# stm32_bob_v2.net
KiCad netlist of a schematic drawn in EAGLE
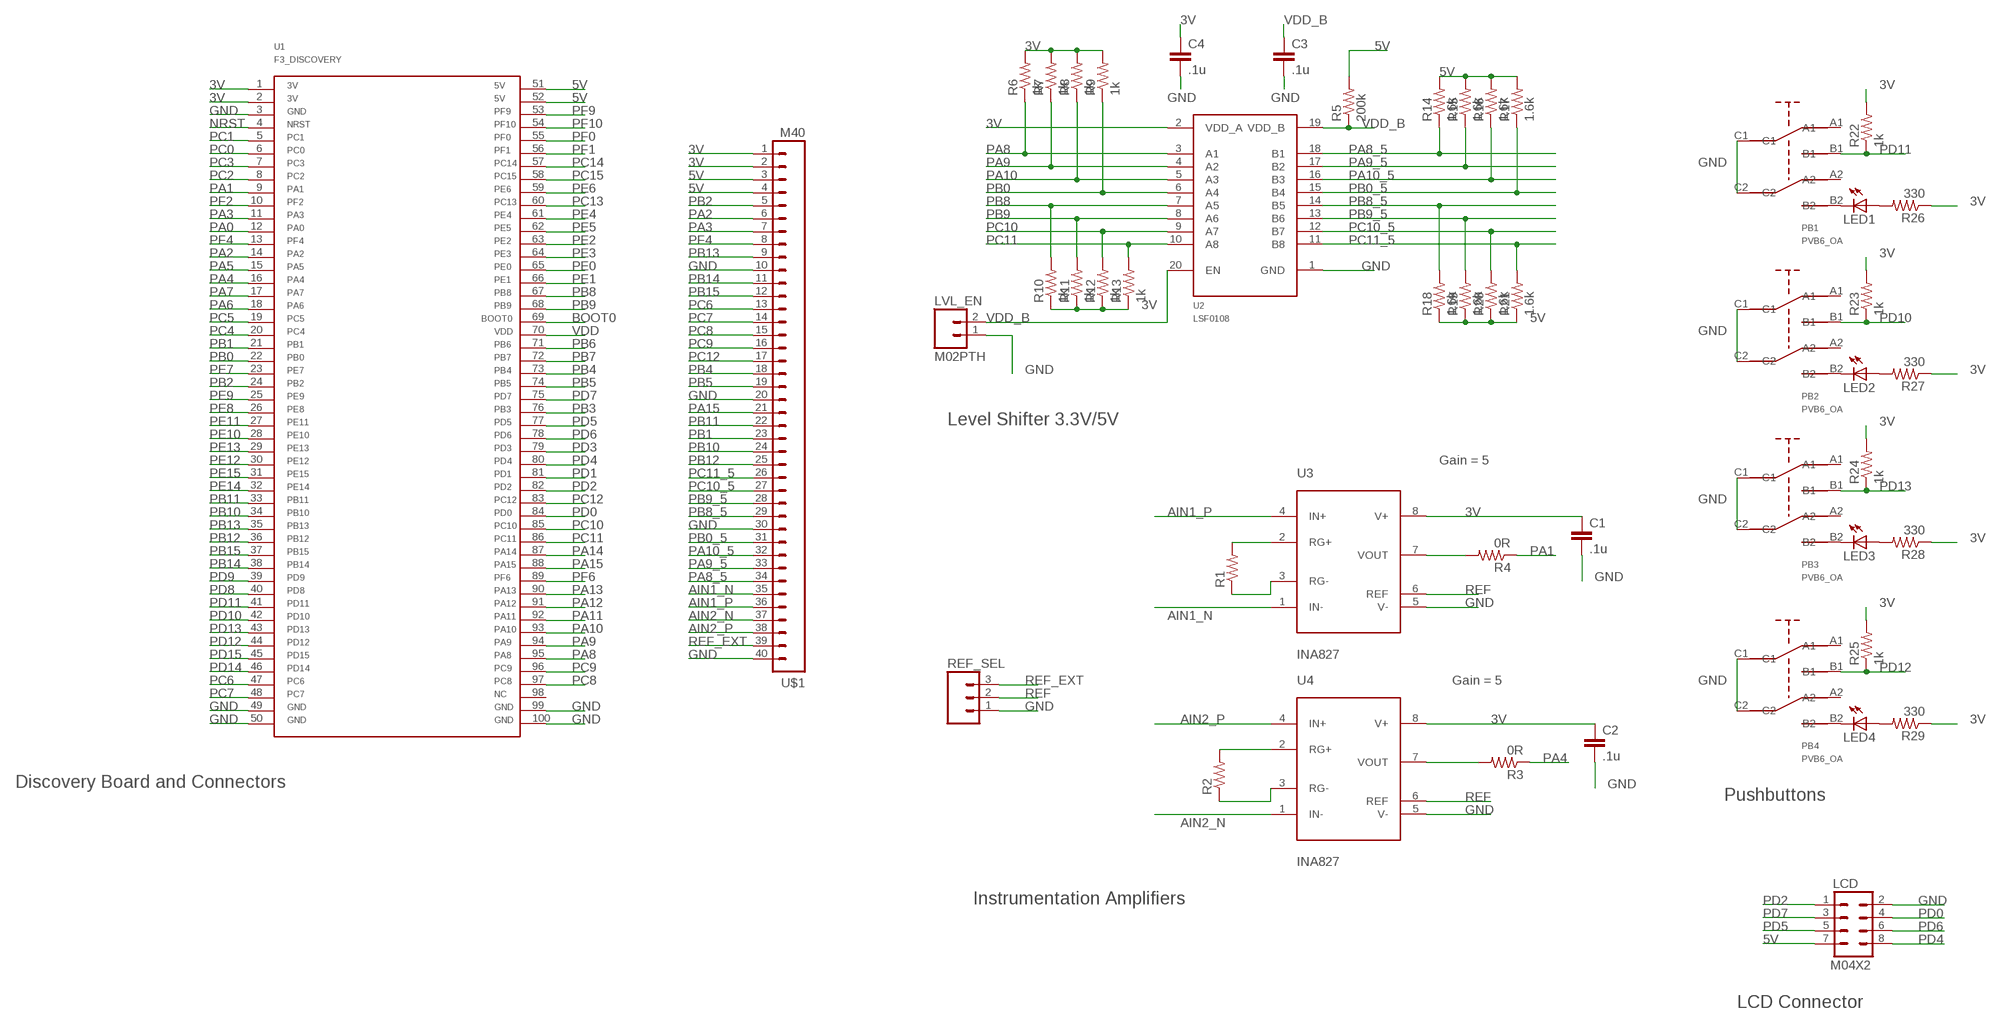
[diagram p0: schematic, sheet 1]

(export (version "E")
  (design (tool "Eeschema 10.0.6"))
  (components
    (comp (ref "C1")
      (value ".1u")
      (footprint "eagle-import:C0805")
      (libsource (lib "eagle-import") (part "C-EUC0805"))
    )
    (comp (ref "C2")
      (value ".1u")
      (footprint "eagle-import:C0805")
      (libsource (lib "eagle-import") (part "C-EUC0805"))
    )
    (comp (ref "C3")
      (value ".1u")
      (footprint "eagle-import:C0805")
      (libsource (lib "eagle-import") (part "C-EUC0805"))
    )
    (comp (ref "C4")
      (value ".1u")
      (footprint "eagle-import:C0805")
      (libsource (lib "eagle-import") (part "C-EUC0805"))
    )
    (comp (ref "LCD")
      (value "M04X2")
      (footprint "eagle-import:2X4")
      (libsource (lib "eagle-import") (part "M04X2"))
    )
    (comp (ref "LED1")
      (value "LED1206")
      (footprint "eagle-import:LED-1206")
      (libsource (lib "eagle-import") (part "LED1206"))
    )
    (comp (ref "LED2")
      (value "LED1206")
      (footprint "eagle-import:LED-1206")
      (libsource (lib "eagle-import") (part "LED1206"))
    )
    (comp (ref "LED3")
      (value "LED1206")
      (footprint "eagle-import:LED-1206")
      (libsource (lib "eagle-import") (part "LED1206"))
    )
    (comp (ref "LED4")
      (value "LED1206")
      (footprint "eagle-import:LED-1206")
      (libsource (lib "eagle-import") (part "LED1206"))
    )
    (comp (ref "LVL_EN")
      (value "M02PTH")
      (footprint "eagle-import:1X02")
      (libsource (lib "eagle-import") (part "M02PTH"))
    )
    (comp (ref "PB1")
      (value "PVB6_OA")
      (footprint "eagle-import:PVB6_OA")
      (libsource (lib "eagle-import") (part "PVB6_OA"))
    )
    (comp (ref "PB2")
      (value "PVB6_OA")
      (footprint "eagle-import:PVB6_OA")
      (libsource (lib "eagle-import") (part "PVB6_OA"))
    )
    (comp (ref "PB3")
      (value "PVB6_OA")
      (footprint "eagle-import:PVB6_OA")
      (libsource (lib "eagle-import") (part "PVB6_OA"))
    )
    (comp (ref "PB4")
      (value "PVB6_OA")
      (footprint "eagle-import:PVB6_OA")
      (libsource (lib "eagle-import") (part "PVB6_OA"))
    )
    (comp (ref "R1")
      (value "R-US_R1206")
      (footprint "eagle-import:R1206")
      (libsource (lib "eagle-import") (part "R-US_R1206"))
    )
    (comp (ref "R2")
      (value "R-US_R1206")
      (footprint "eagle-import:R1206")
      (libsource (lib "eagle-import") (part "R-US_R1206"))
    )
    (comp (ref "R3")
      (value "0R")
      (footprint "eagle-import:R1206")
      (libsource (lib "eagle-import") (part "R-US_R1206"))
    )
    (comp (ref "R4")
      (value "0R")
      (footprint "eagle-import:R1206")
      (libsource (lib "eagle-import") (part "R-US_R1206"))
    )
    (comp (ref "R5")
      (value "200k")
      (footprint "eagle-import:R0805")
      (libsource (lib "eagle-import") (part "R-US_R0805"))
    )
    (comp (ref "R6")
      (value "1k")
      (footprint "eagle-import:R0805")
      (libsource (lib "eagle-import") (part "R-US_R0805"))
    )
    (comp (ref "R7")
      (value "1k")
      (footprint "eagle-import:R0805")
      (libsource (lib "eagle-import") (part "R-US_R0805"))
    )
    (comp (ref "R8")
      (value "1k")
      (footprint "eagle-import:R0805")
      (libsource (lib "eagle-import") (part "R-US_R0805"))
    )
    (comp (ref "R9")
      (value "1k")
      (footprint "eagle-import:R0805")
      (libsource (lib "eagle-import") (part "R-US_R0805"))
    )
    (comp (ref "R10")
      (value "1k")
      (footprint "eagle-import:R0805")
      (libsource (lib "eagle-import") (part "R-US_R0805"))
    )
    (comp (ref "R11")
      (value "1k")
      (footprint "eagle-import:R0805")
      (libsource (lib "eagle-import") (part "R-US_R0805"))
    )
    (comp (ref "R12")
      (value "1k")
      (footprint "eagle-import:R0805")
      (libsource (lib "eagle-import") (part "R-US_R0805"))
    )
    (comp (ref "R13")
      (value "1k")
      (footprint "eagle-import:R0805")
      (libsource (lib "eagle-import") (part "R-US_R0805"))
    )
    (comp (ref "R14")
      (value "1.6k")
      (footprint "eagle-import:R0805")
      (libsource (lib "eagle-import") (part "R-US_R0805"))
    )
    (comp (ref "R15")
      (value "1.6k")
      (footprint "eagle-import:R0805")
      (libsource (lib "eagle-import") (part "R-US_R0805"))
    )
    (comp (ref "R16")
      (value "1.6k")
      (footprint "eagle-import:R0805")
      (libsource (lib "eagle-import") (part "R-US_R0805"))
    )
    (comp (ref "R17")
      (value "1.6k")
      (footprint "eagle-import:R0805")
      (libsource (lib "eagle-import") (part "R-US_R0805"))
    )
    (comp (ref "R18")
      (value "1.6k")
      (footprint "eagle-import:R0805")
      (libsource (lib "eagle-import") (part "R-US_R0805"))
    )
    (comp (ref "R19")
      (value "1.6k")
      (footprint "eagle-import:R0805")
      (libsource (lib "eagle-import") (part "R-US_R0805"))
    )
    (comp (ref "R20")
      (value "1.6k")
      (footprint "eagle-import:R0805")
      (libsource (lib "eagle-import") (part "R-US_R0805"))
    )
    (comp (ref "R21")
      (value "1.6k")
      (footprint "eagle-import:R0805")
      (libsource (lib "eagle-import") (part "R-US_R0805"))
    )
    (comp (ref "R22")
      (value "1k")
      (footprint "eagle-import:R0805")
      (libsource (lib "eagle-import") (part "R-US_R0805"))
    )
    (comp (ref "R23")
      (value "1k")
      (footprint "eagle-import:R0805")
      (libsource (lib "eagle-import") (part "R-US_R0805"))
    )
    (comp (ref "R24")
      (value "1k")
      (footprint "eagle-import:R0805")
      (libsource (lib "eagle-import") (part "R-US_R0805"))
    )
    (comp (ref "R25")
      (value "1k")
      (footprint "eagle-import:R0805")
      (libsource (lib "eagle-import") (part "R-US_R0805"))
    )
    (comp (ref "R26")
      (value "330")
      (footprint "eagle-import:R0805")
      (libsource (lib "eagle-import") (part "R-US_R0805"))
    )
    (comp (ref "R27")
      (value "330")
      (footprint "eagle-import:R0805")
      (libsource (lib "eagle-import") (part "R-US_R0805"))
    )
    (comp (ref "R28")
      (value "330")
      (footprint "eagle-import:R0805")
      (libsource (lib "eagle-import") (part "R-US_R0805"))
    )
    (comp (ref "R29")
      (value "330")
      (footprint "eagle-import:R0805")
      (libsource (lib "eagle-import") (part "R-US_R0805"))
    )
    (comp (ref "REF_SEL")
      (value "M03PTH")
      (footprint "eagle-import:1X03")
      (libsource (lib "eagle-import") (part "M03PTH"))
    )
    (comp (ref "U$1")
      (value "M40")
      (footprint "eagle-import:1X40")
      (libsource (lib "eagle-import") (part "M40"))
    )
    (comp (ref "U1")
      (value "F3_DISCOVERY")
      (footprint "eagle-import:F3_DISCOVERY")
      (libsource (lib "eagle-import") (part "F3_DISCOVERY"))
    )
    (comp (ref "U2")
      (value "LSF0108")
      (footprint "eagle-import:LSF0108")
      (libsource (lib "eagle-import") (part "LSF0108"))
    )
    (comp (ref "U3")
      (value "INA827")
      (footprint "eagle-import:MSOP8")
      (libsource (lib "eagle-import") (part "INA827"))
    )
    (comp (ref "U4")
      (value "INA827")
      (footprint "eagle-import:MSOP8")
      (libsource (lib "eagle-import") (part "INA827"))
    )
  )
  (nets
    (net (code "1") (name "/3V") (class "Default")
      (node (ref "C1") (pin "1") (pinfunction "1_1") (pintype "passive"))
      (node (ref "C2") (pin "1") (pinfunction "1_1") (pintype "passive"))
      (node (ref "C4") (pin "1") (pinfunction "1_1") (pintype "passive"))
      (node (ref "R10") (pin "1") (pinfunction "1_1") (pintype "passive"))
      (node (ref "R11") (pin "1") (pinfunction "1_1") (pintype "passive"))
      (node (ref "R12") (pin "1") (pinfunction "1_1") (pintype "passive"))
      (node (ref "R13") (pin "1") (pinfunction "1_1") (pintype "passive"))
      (node (ref "R22") (pin "2") (pinfunction "2_2") (pintype "passive"))
      (node (ref "R23") (pin "2") (pinfunction "2_2") (pintype "passive"))
      (node (ref "R24") (pin "2") (pinfunction "2_2") (pintype "passive"))
      (node (ref "R25") (pin "2") (pinfunction "2_2") (pintype "passive"))
      (node (ref "R26") (pin "1") (pinfunction "1_1") (pintype "passive"))
      (node (ref "R27") (pin "1") (pinfunction "1_1") (pintype "passive"))
      (node (ref "R28") (pin "1") (pinfunction "1_1") (pintype "passive"))
      (node (ref "R29") (pin "1") (pinfunction "1_1") (pintype "passive"))
      (node (ref "R6") (pin "2") (pinfunction "2_2") (pintype "passive"))
      (node (ref "R7") (pin "2") (pinfunction "2_2") (pintype "passive"))
      (node (ref "R8") (pin "2") (pinfunction "2_2") (pintype "passive"))
      (node (ref "R9") (pin "2") (pinfunction "2_2") (pintype "passive"))
      (node (ref "U$1") (pin "1") (pinfunction "1_1") (pintype "passive"))
      (node (ref "U$1") (pin "2") (pinfunction "2_2") (pintype "passive"))
      (node (ref "U1") (pin "1") (pinfunction "P$1_1") (pintype "bidirectional"))
      (node (ref "U1") (pin "2") (pinfunction "P$2_2") (pintype "bidirectional"))
      (node (ref "U2") (pin "2") (pinfunction "VDD_A_2") (pintype "bidirectional"))
      (node (ref "U3") (pin "8") (pinfunction "V+_8") (pintype "bidirectional"))
      (node (ref "U4") (pin "8") (pinfunction "V+_8") (pintype "bidirectional"))
    )
    (net (code "2") (name "/5V") (class "Default")
      (node (ref "LCD") (pin "7") (pinfunction "7_7") (pintype "passive"))
      (node (ref "R14") (pin "2") (pinfunction "2_2") (pintype "passive"))
      (node (ref "R15") (pin "2") (pinfunction "2_2") (pintype "passive"))
      (node (ref "R16") (pin "2") (pinfunction "2_2") (pintype "passive"))
      (node (ref "R17") (pin "2") (pinfunction "2_2") (pintype "passive"))
      (node (ref "R18") (pin "1") (pinfunction "1_1") (pintype "passive"))
      (node (ref "R19") (pin "1") (pinfunction "1_1") (pintype "passive"))
      (node (ref "R20") (pin "1") (pinfunction "1_1") (pintype "passive"))
      (node (ref "R21") (pin "1") (pinfunction "1_1") (pintype "passive"))
      (node (ref "R5") (pin "2") (pinfunction "2_2") (pintype "passive"))
      (node (ref "U$1") (pin "3") (pinfunction "3_3") (pintype "passive"))
      (node (ref "U$1") (pin "4") (pinfunction "4_4") (pintype "passive"))
      (node (ref "U1") (pin "51") (pinfunction "P$51_51") (pintype "bidirectional"))
      (node (ref "U1") (pin "52") (pinfunction "P$52_52") (pintype "bidirectional"))
    )
    (net (code "3") (name "/AIN1_N") (class "Default")
      (node (ref "U$1") (pin "35") (pinfunction "35_35") (pintype "passive"))
      (node (ref "U3") (pin "1") (pinfunction "IN-_1") (pintype "bidirectional"))
    )
    (net (code "4") (name "/AIN1_P") (class "Default")
      (node (ref "U$1") (pin "36") (pinfunction "36_36") (pintype "passive"))
      (node (ref "U3") (pin "4") (pinfunction "IN+_4") (pintype "bidirectional"))
    )
    (net (code "5") (name "/AIN2_N") (class "Default")
      (node (ref "U$1") (pin "37") (pinfunction "37_37") (pintype "passive"))
      (node (ref "U4") (pin "1") (pinfunction "IN-_1") (pintype "bidirectional"))
    )
    (net (code "6") (name "/AIN2_P") (class "Default")
      (node (ref "U$1") (pin "38") (pinfunction "38_38") (pintype "passive"))
      (node (ref "U4") (pin "4") (pinfunction "IN+_4") (pintype "bidirectional"))
    )
    (net (code "7") (name "/BOOT0") (class "Default")
      (node (ref "U1") (pin "69") (pinfunction "P$69_69") (pintype "bidirectional"))
    )
    (net (code "8") (name "/GND") (class "Default")
      (node (ref "C1") (pin "2") (pinfunction "2_2") (pintype "passive"))
      (node (ref "C2") (pin "2") (pinfunction "2_2") (pintype "passive"))
      (node (ref "C3") (pin "2") (pinfunction "2_2") (pintype "passive"))
      (node (ref "C4") (pin "2") (pinfunction "2_2") (pintype "passive"))
      (node (ref "LCD") (pin "2") (pinfunction "2_2") (pintype "passive"))
      (node (ref "LVL_EN") (pin "1") (pinfunction "1_1") (pintype "passive"))
      (node (ref "PB1") (pin "C1") (pinfunction "C1_C1") (pintype "bidirectional"))
      (node (ref "PB1") (pin "C2") (pinfunction "C2_C2") (pintype "bidirectional"))
      (node (ref "PB2") (pin "C1") (pinfunction "C1_C1") (pintype "bidirectional"))
      (node (ref "PB2") (pin "C2") (pinfunction "C2_C2") (pintype "bidirectional"))
      (node (ref "PB3") (pin "C1") (pinfunction "C1_C1") (pintype "bidirectional"))
      (node (ref "PB3") (pin "C2") (pinfunction "C2_C2") (pintype "bidirectional"))
      (node (ref "PB4") (pin "C1") (pinfunction "C1_C1") (pintype "bidirectional"))
      (node (ref "PB4") (pin "C2") (pinfunction "C2_C2") (pintype "bidirectional"))
      (node (ref "REF_SEL") (pin "1") (pinfunction "1_1") (pintype "passive"))
      (node (ref "U$1") (pin "10") (pinfunction "10_10") (pintype "passive"))
      (node (ref "U$1") (pin "20") (pinfunction "20_20") (pintype "passive"))
      (node (ref "U$1") (pin "30") (pinfunction "30_30") (pintype "passive"))
      (node (ref "U$1") (pin "40") (pinfunction "40_40") (pintype "passive"))
      (node (ref "U1") (pin "100") (pinfunction "P$100_100") (pintype "bidirectional"))
      (node (ref "U1") (pin "3") (pinfunction "P$3_3") (pintype "bidirectional"))
      (node (ref "U1") (pin "49") (pinfunction "P$49_49") (pintype "bidirectional"))
      (node (ref "U1") (pin "50") (pinfunction "P$50_50") (pintype "bidirectional"))
      (node (ref "U1") (pin "99") (pinfunction "P$99_99") (pintype "bidirectional"))
      (node (ref "U2") (pin "1") (pinfunction "GND_1") (pintype "bidirectional"))
      (node (ref "U3") (pin "5") (pinfunction "V-_5") (pintype "bidirectional"))
      (node (ref "U4") (pin "5") (pinfunction "V-_5") (pintype "bidirectional"))
    )
    (net (code "9") (name "/NRST") (class "Default")
      (node (ref "U1") (pin "4") (pinfunction "P$4_4") (pintype "bidirectional"))
    )
    (net (code "10") (name "/PA0") (class "Default")
      (node (ref "U1") (pin "12") (pinfunction "P$12_12") (pintype "bidirectional"))
    )
    (net (code "11") (name "/PA1") (class "Default")
      (node (ref "R4") (pin "1") (pinfunction "1_1") (pintype "passive"))
      (node (ref "U1") (pin "9") (pinfunction "P$9_9") (pintype "bidirectional"))
    )
    (net (code "12") (name "/PA2") (class "Default")
      (node (ref "U$1") (pin "6") (pinfunction "6_6") (pintype "passive"))
      (node (ref "U1") (pin "14") (pinfunction "P$14_14") (pintype "bidirectional"))
    )
    (net (code "13") (name "/PA3") (class "Default")
      (node (ref "U$1") (pin "7") (pinfunction "7_7") (pintype "passive"))
      (node (ref "U1") (pin "11") (pinfunction "P$11_11") (pintype "bidirectional"))
    )
    (net (code "14") (name "/PA4") (class "Default")
      (node (ref "R3") (pin "1") (pinfunction "1_1") (pintype "passive"))
      (node (ref "U1") (pin "16") (pinfunction "P$16_16") (pintype "bidirectional"))
    )
    (net (code "15") (name "/PA5") (class "Default")
      (node (ref "U1") (pin "15") (pinfunction "P$15_15") (pintype "bidirectional"))
    )
    (net (code "16") (name "/PA6") (class "Default")
      (node (ref "U1") (pin "18") (pinfunction "P$18_18") (pintype "bidirectional"))
    )
    (net (code "17") (name "/PA7") (class "Default")
      (node (ref "U1") (pin "17") (pinfunction "P$17_17") (pintype "bidirectional"))
    )
    (net (code "18") (name "/PA8") (class "Default")
      (node (ref "R6") (pin "1") (pinfunction "1_1") (pintype "passive"))
      (node (ref "U1") (pin "95") (pinfunction "P$95_95") (pintype "bidirectional"))
      (node (ref "U2") (pin "3") (pinfunction "A1_3") (pintype "bidirectional"))
    )
    (net (code "19") (name "/PA8_5") (class "Default")
      (node (ref "R14") (pin "1") (pinfunction "1_1") (pintype "passive"))
      (node (ref "U$1") (pin "34") (pinfunction "34_34") (pintype "passive"))
      (node (ref "U2") (pin "18") (pinfunction "B1_18") (pintype "bidirectional"))
    )
    (net (code "20") (name "/PA9") (class "Default")
      (node (ref "R7") (pin "1") (pinfunction "1_1") (pintype "passive"))
      (node (ref "U1") (pin "94") (pinfunction "P$94_94") (pintype "bidirectional"))
      (node (ref "U2") (pin "4") (pinfunction "A2_4") (pintype "bidirectional"))
    )
    (net (code "21") (name "/PA9_5") (class "Default")
      (node (ref "R15") (pin "1") (pinfunction "1_1") (pintype "passive"))
      (node (ref "U$1") (pin "33") (pinfunction "33_33") (pintype "passive"))
      (node (ref "U2") (pin "17") (pinfunction "B2_17") (pintype "bidirectional"))
    )
    (net (code "22") (name "/PA10") (class "Default")
      (node (ref "R8") (pin "1") (pinfunction "1_1") (pintype "passive"))
      (node (ref "U1") (pin "93") (pinfunction "P$93_93") (pintype "bidirectional"))
      (node (ref "U2") (pin "5") (pinfunction "A3_5") (pintype "bidirectional"))
    )
    (net (code "23") (name "/PA10_5") (class "Default")
      (node (ref "R16") (pin "1") (pinfunction "1_1") (pintype "passive"))
      (node (ref "U$1") (pin "32") (pinfunction "32_32") (pintype "passive"))
      (node (ref "U2") (pin "16") (pinfunction "B3_16") (pintype "bidirectional"))
    )
    (net (code "24") (name "/PA11") (class "Default")
      (node (ref "U1") (pin "92") (pinfunction "P$92_92") (pintype "bidirectional"))
    )
    (net (code "25") (name "/PA12") (class "Default")
      (node (ref "U1") (pin "91") (pinfunction "P$91_91") (pintype "bidirectional"))
    )
    (net (code "26") (name "/PA13") (class "Default")
      (node (ref "U1") (pin "90") (pinfunction "P$90_90") (pintype "bidirectional"))
    )
    (net (code "27") (name "/PA14") (class "Default")
      (node (ref "U1") (pin "87") (pinfunction "P$87_87") (pintype "bidirectional"))
    )
    (net (code "28") (name "/PA15") (class "Default")
      (node (ref "U$1") (pin "21") (pinfunction "21_21") (pintype "passive"))
      (node (ref "U1") (pin "88") (pinfunction "P$88_88") (pintype "bidirectional"))
    )
    (net (code "29") (name "/PB0") (class "Default")
      (node (ref "R9") (pin "1") (pinfunction "1_1") (pintype "passive"))
      (node (ref "U1") (pin "22") (pinfunction "P$22_22") (pintype "bidirectional"))
      (node (ref "U2") (pin "6") (pinfunction "A4_6") (pintype "bidirectional"))
    )
    (net (code "30") (name "/PB0_5") (class "Default")
      (node (ref "R17") (pin "1") (pinfunction "1_1") (pintype "passive"))
      (node (ref "U$1") (pin "31") (pinfunction "31_31") (pintype "passive"))
      (node (ref "U2") (pin "15") (pinfunction "B4_15") (pintype "bidirectional"))
    )
    (net (code "31") (name "/PB1") (class "Default")
      (node (ref "U$1") (pin "23") (pinfunction "23_23") (pintype "passive"))
      (node (ref "U1") (pin "21") (pinfunction "P$21_21") (pintype "bidirectional"))
    )
    (net (code "32") (name "/PB2") (class "Default")
      (node (ref "U$1") (pin "5") (pinfunction "5_5") (pintype "passive"))
      (node (ref "U1") (pin "24") (pinfunction "P$24_24") (pintype "bidirectional"))
    )
    (net (code "33") (name "/PB3") (class "Default")
      (node (ref "U1") (pin "76") (pinfunction "P$76_76") (pintype "bidirectional"))
    )
    (net (code "34") (name "/PB4") (class "Default")
      (node (ref "U$1") (pin "18") (pinfunction "18_18") (pintype "passive"))
      (node (ref "U1") (pin "73") (pinfunction "P$73_73") (pintype "bidirectional"))
    )
    (net (code "35") (name "/PB5") (class "Default")
      (node (ref "U$1") (pin "19") (pinfunction "19_19") (pintype "passive"))
      (node (ref "U1") (pin "74") (pinfunction "P$74_74") (pintype "bidirectional"))
    )
    (net (code "36") (name "/PB6") (class "Default")
      (node (ref "U1") (pin "71") (pinfunction "P$71_71") (pintype "bidirectional"))
    )
    (net (code "37") (name "/PB7") (class "Default")
      (node (ref "U1") (pin "72") (pinfunction "P$72_72") (pintype "bidirectional"))
    )
    (net (code "38") (name "/PB8") (class "Default")
      (node (ref "R10") (pin "2") (pinfunction "2_2") (pintype "passive"))
      (node (ref "U1") (pin "67") (pinfunction "P$67_67") (pintype "bidirectional"))
      (node (ref "U2") (pin "7") (pinfunction "A5_7") (pintype "bidirectional"))
    )
    (net (code "39") (name "/PB8_5") (class "Default")
      (node (ref "R18") (pin "2") (pinfunction "2_2") (pintype "passive"))
      (node (ref "U$1") (pin "29") (pinfunction "29_29") (pintype "passive"))
      (node (ref "U2") (pin "14") (pinfunction "B5_14") (pintype "bidirectional"))
    )
    (net (code "40") (name "/PB9") (class "Default")
      (node (ref "R11") (pin "2") (pinfunction "2_2") (pintype "passive"))
      (node (ref "U1") (pin "68") (pinfunction "P$68_68") (pintype "bidirectional"))
      (node (ref "U2") (pin "8") (pinfunction "A6_8") (pintype "bidirectional"))
    )
    (net (code "41") (name "/PB9_5") (class "Default")
      (node (ref "R19") (pin "2") (pinfunction "2_2") (pintype "passive"))
      (node (ref "U$1") (pin "28") (pinfunction "28_28") (pintype "passive"))
      (node (ref "U2") (pin "13") (pinfunction "B6_13") (pintype "bidirectional"))
    )
    (net (code "42") (name "/PB10") (class "Default")
      (node (ref "U$1") (pin "24") (pinfunction "24_24") (pintype "passive"))
      (node (ref "U1") (pin "34") (pinfunction "P$34_34") (pintype "bidirectional"))
    )
    (net (code "43") (name "/PB11") (class "Default")
      (node (ref "U$1") (pin "22") (pinfunction "22_22") (pintype "passive"))
      (node (ref "U1") (pin "33") (pinfunction "P$33_33") (pintype "bidirectional"))
    )
    (net (code "44") (name "/PB12") (class "Default")
      (node (ref "U$1") (pin "25") (pinfunction "25_25") (pintype "passive"))
      (node (ref "U1") (pin "36") (pinfunction "P$36_36") (pintype "bidirectional"))
    )
    (net (code "45") (name "/PB13") (class "Default")
      (node (ref "U$1") (pin "9") (pinfunction "9_9") (pintype "passive"))
      (node (ref "U1") (pin "35") (pinfunction "P$35_35") (pintype "bidirectional"))
    )
    (net (code "46") (name "/PB14") (class "Default")
      (node (ref "U$1") (pin "11") (pinfunction "11_11") (pintype "passive"))
      (node (ref "U1") (pin "38") (pinfunction "P$38_38") (pintype "bidirectional"))
    )
    (net (code "47") (name "/PB15") (class "Default")
      (node (ref "U$1") (pin "12") (pinfunction "12_12") (pintype "passive"))
      (node (ref "U1") (pin "37") (pinfunction "P$37_37") (pintype "bidirectional"))
    )
    (net (code "48") (name "/PC0") (class "Default")
      (node (ref "U1") (pin "6") (pinfunction "P$6_6") (pintype "bidirectional"))
    )
    (net (code "49") (name "/PC1") (class "Default")
      (node (ref "U1") (pin "5") (pinfunction "P$5_5") (pintype "bidirectional"))
    )
    (net (code "50") (name "/PC2") (class "Default")
      (node (ref "U1") (pin "8") (pinfunction "P$8_8") (pintype "bidirectional"))
    )
    (net (code "51") (name "/PC3") (class "Default")
      (node (ref "U1") (pin "7") (pinfunction "P$7_7") (pintype "bidirectional"))
    )
    (net (code "52") (name "/PC4") (class "Default")
      (node (ref "U1") (pin "20") (pinfunction "P$20_20") (pintype "bidirectional"))
    )
    (net (code "53") (name "/PC5") (class "Default")
      (node (ref "U1") (pin "19") (pinfunction "P$19_19") (pintype "bidirectional"))
    )
    (net (code "54") (name "/PC6") (class "Default")
      (node (ref "U$1") (pin "13") (pinfunction "13_13") (pintype "passive"))
      (node (ref "U1") (pin "47") (pinfunction "P$47_47") (pintype "bidirectional"))
    )
    (net (code "55") (name "/PC7") (class "Default")
      (node (ref "U$1") (pin "14") (pinfunction "14_14") (pintype "passive"))
      (node (ref "U1") (pin "48") (pinfunction "P$48_48") (pintype "bidirectional"))
    )
    (net (code "56") (name "/PC8") (class "Default")
      (node (ref "U$1") (pin "15") (pinfunction "15_15") (pintype "passive"))
      (node (ref "U1") (pin "97") (pinfunction "P$97_97") (pintype "bidirectional"))
    )
    (net (code "57") (name "/PC9") (class "Default")
      (node (ref "U$1") (pin "16") (pinfunction "16_16") (pintype "passive"))
      (node (ref "U1") (pin "96") (pinfunction "P$96_96") (pintype "bidirectional"))
    )
    (net (code "58") (name "/PC10") (class "Default")
      (node (ref "R12") (pin "2") (pinfunction "2_2") (pintype "passive"))
      (node (ref "U1") (pin "85") (pinfunction "P$85_85") (pintype "bidirectional"))
      (node (ref "U2") (pin "9") (pinfunction "A7_9") (pintype "bidirectional"))
    )
    (net (code "59") (name "/PC10_5") (class "Default")
      (node (ref "R20") (pin "2") (pinfunction "2_2") (pintype "passive"))
      (node (ref "U$1") (pin "27") (pinfunction "27_27") (pintype "passive"))
      (node (ref "U2") (pin "12") (pinfunction "B7_12") (pintype "bidirectional"))
    )
    (net (code "60") (name "/PC11") (class "Default")
      (node (ref "R13") (pin "2") (pinfunction "2_2") (pintype "passive"))
      (node (ref "U1") (pin "86") (pinfunction "P$86_86") (pintype "bidirectional"))
      (node (ref "U2") (pin "10") (pinfunction "A8_10") (pintype "bidirectional"))
    )
    (net (code "61") (name "/PC11_5") (class "Default")
      (node (ref "R21") (pin "2") (pinfunction "2_2") (pintype "passive"))
      (node (ref "U$1") (pin "26") (pinfunction "26_26") (pintype "passive"))
      (node (ref "U2") (pin "11") (pinfunction "B8_11") (pintype "bidirectional"))
    )
    (net (code "62") (name "/PC12") (class "Default")
      (node (ref "U$1") (pin "17") (pinfunction "17_17") (pintype "passive"))
      (node (ref "U1") (pin "83") (pinfunction "P$83_83") (pintype "bidirectional"))
    )
    (net (code "63") (name "/PC13") (class "Default")
      (node (ref "U1") (pin "60") (pinfunction "P$60_60") (pintype "bidirectional"))
    )
    (net (code "64") (name "/PC14") (class "Default")
      (node (ref "U1") (pin "57") (pinfunction "P$57_57") (pintype "bidirectional"))
    )
    (net (code "65") (name "/PC15") (class "Default")
      (node (ref "U1") (pin "58") (pinfunction "P$58_58") (pintype "bidirectional"))
    )
    (net (code "66") (name "/PD0") (class "Default")
      (node (ref "LCD") (pin "4") (pinfunction "4_4") (pintype "passive"))
      (node (ref "U1") (pin "84") (pinfunction "P$84_84") (pintype "bidirectional"))
    )
    (net (code "67") (name "/PD1") (class "Default")
      (node (ref "U1") (pin "81") (pinfunction "P$81_81") (pintype "bidirectional"))
    )
    (net (code "68") (name "/PD2") (class "Default")
      (node (ref "LCD") (pin "1") (pinfunction "1_1") (pintype "passive"))
      (node (ref "U1") (pin "82") (pinfunction "P$82_82") (pintype "bidirectional"))
    )
    (net (code "69") (name "/PD3") (class "Default")
      (node (ref "U1") (pin "79") (pinfunction "P$79_79") (pintype "bidirectional"))
    )
    (net (code "70") (name "/PD4") (class "Default")
      (node (ref "LCD") (pin "8") (pinfunction "8_8") (pintype "passive"))
      (node (ref "U1") (pin "80") (pinfunction "P$80_80") (pintype "bidirectional"))
    )
    (net (code "71") (name "/PD5") (class "Default")
      (node (ref "LCD") (pin "5") (pinfunction "5_5") (pintype "passive"))
      (node (ref "U1") (pin "77") (pinfunction "P$77_77") (pintype "bidirectional"))
    )
    (net (code "72") (name "/PD6") (class "Default")
      (node (ref "LCD") (pin "6") (pinfunction "6_6") (pintype "passive"))
      (node (ref "U1") (pin "78") (pinfunction "P$78_78") (pintype "bidirectional"))
    )
    (net (code "73") (name "/PD7") (class "Default")
      (node (ref "LCD") (pin "3") (pinfunction "3_3") (pintype "passive"))
      (node (ref "U1") (pin "75") (pinfunction "P$75_75") (pintype "bidirectional"))
    )
    (net (code "74") (name "/PD8") (class "Default")
      (node (ref "U1") (pin "40") (pinfunction "P$40_40") (pintype "bidirectional"))
    )
    (net (code "75") (name "/PD9") (class "Default")
      (node (ref "U1") (pin "39") (pinfunction "P$39_39") (pintype "bidirectional"))
    )
    (net (code "76") (name "/PD10") (class "Default")
      (node (ref "PB2") (pin "B1") (pinfunction "B1_B1") (pintype "bidirectional"))
      (node (ref "R23") (pin "1") (pinfunction "1_1") (pintype "passive"))
      (node (ref "U1") (pin "42") (pinfunction "P$42_42") (pintype "bidirectional"))
    )
    (net (code "77") (name "/PD11") (class "Default")
      (node (ref "PB1") (pin "B1") (pinfunction "B1_B1") (pintype "bidirectional"))
      (node (ref "R22") (pin "1") (pinfunction "1_1") (pintype "passive"))
      (node (ref "U1") (pin "41") (pinfunction "P$41_41") (pintype "bidirectional"))
    )
    (net (code "78") (name "/PD12") (class "Default")
      (node (ref "PB4") (pin "B1") (pinfunction "B1_B1") (pintype "bidirectional"))
      (node (ref "R25") (pin "1") (pinfunction "1_1") (pintype "passive"))
      (node (ref "U1") (pin "44") (pinfunction "P$44_44") (pintype "bidirectional"))
    )
    (net (code "79") (name "/PD13") (class "Default")
      (node (ref "PB3") (pin "B1") (pinfunction "B1_B1") (pintype "bidirectional"))
      (node (ref "R24") (pin "1") (pinfunction "1_1") (pintype "passive"))
      (node (ref "U1") (pin "43") (pinfunction "P$43_43") (pintype "bidirectional"))
    )
    (net (code "80") (name "/PD14") (class "Default")
      (node (ref "U1") (pin "46") (pinfunction "P$46_46") (pintype "bidirectional"))
    )
    (net (code "81") (name "/PD15") (class "Default")
      (node (ref "U1") (pin "45") (pinfunction "P$45_45") (pintype "bidirectional"))
    )
    (net (code "82") (name "/PE0") (class "Default")
      (node (ref "U1") (pin "65") (pinfunction "P$65_65") (pintype "bidirectional"))
    )
    (net (code "83") (name "/PE1") (class "Default")
      (node (ref "U1") (pin "66") (pinfunction "P$66_66") (pintype "bidirectional"))
    )
    (net (code "84") (name "/PE2") (class "Default")
      (node (ref "U1") (pin "63") (pinfunction "P$63_63") (pintype "bidirectional"))
    )
    (net (code "85") (name "/PE3") (class "Default")
      (node (ref "U1") (pin "64") (pinfunction "P$64_64") (pintype "bidirectional"))
    )
    (net (code "86") (name "/PE4") (class "Default")
      (node (ref "U1") (pin "61") (pinfunction "P$61_61") (pintype "bidirectional"))
    )
    (net (code "87") (name "/PE5") (class "Default")
      (node (ref "U1") (pin "62") (pinfunction "P$62_62") (pintype "bidirectional"))
    )
    (net (code "88") (name "/PE6") (class "Default")
      (node (ref "U1") (pin "59") (pinfunction "P$59_59") (pintype "bidirectional"))
    )
    (net (code "89") (name "/PE7") (class "Default")
      (node (ref "U1") (pin "23") (pinfunction "P$23_23") (pintype "bidirectional"))
    )
    (net (code "90") (name "/PE8") (class "Default")
      (node (ref "U1") (pin "26") (pinfunction "P$26_26") (pintype "bidirectional"))
    )
    (net (code "91") (name "/PE9") (class "Default")
      (node (ref "U1") (pin "25") (pinfunction "P$25_25") (pintype "bidirectional"))
    )
    (net (code "92") (name "/PE10") (class "Default")
      (node (ref "U1") (pin "28") (pinfunction "P$28_28") (pintype "bidirectional"))
    )
    (net (code "93") (name "/PE11") (class "Default")
      (node (ref "U1") (pin "27") (pinfunction "P$27_27") (pintype "bidirectional"))
    )
    (net (code "94") (name "/PE12") (class "Default")
      (node (ref "U1") (pin "30") (pinfunction "P$30_30") (pintype "bidirectional"))
    )
    (net (code "95") (name "/PE13") (class "Default")
      (node (ref "U1") (pin "29") (pinfunction "P$29_29") (pintype "bidirectional"))
    )
    (net (code "96") (name "/PE14") (class "Default")
      (node (ref "U1") (pin "32") (pinfunction "P$32_32") (pintype "bidirectional"))
    )
    (net (code "97") (name "/PE15") (class "Default")
      (node (ref "U1") (pin "31") (pinfunction "P$31_31") (pintype "bidirectional"))
    )
    (net (code "98") (name "/PF0") (class "Default")
      (node (ref "U1") (pin "55") (pinfunction "P$55_55") (pintype "bidirectional"))
    )
    (net (code "99") (name "/PF1") (class "Default")
      (node (ref "U1") (pin "56") (pinfunction "P$56_56") (pintype "bidirectional"))
    )
    (net (code "100") (name "/PF2") (class "Default")
      (node (ref "U1") (pin "10") (pinfunction "P$10_10") (pintype "bidirectional"))
    )
    (net (code "101") (name "/PF4") (class "Default")
      (node (ref "U$1") (pin "8") (pinfunction "8_8") (pintype "passive"))
      (node (ref "U1") (pin "13") (pinfunction "P$13_13") (pintype "bidirectional"))
    )
    (net (code "102") (name "/PF6") (class "Default")
      (node (ref "U1") (pin "89") (pinfunction "P$89_89") (pintype "bidirectional"))
    )
    (net (code "103") (name "/PF9") (class "Default")
      (node (ref "U1") (pin "53") (pinfunction "P$53_53") (pintype "bidirectional"))
    )
    (net (code "104") (name "/PF10") (class "Default")
      (node (ref "U1") (pin "54") (pinfunction "P$54_54") (pintype "bidirectional"))
    )
    (net (code "105") (name "/REF") (class "Default")
      (node (ref "REF_SEL") (pin "2") (pinfunction "2_2") (pintype "passive"))
      (node (ref "U3") (pin "6") (pinfunction "REF_6") (pintype "bidirectional"))
      (node (ref "U4") (pin "6") (pinfunction "REF_6") (pintype "bidirectional"))
    )
    (net (code "106") (name "/REF_EXT") (class "Default")
      (node (ref "REF_SEL") (pin "3") (pinfunction "3_3") (pintype "passive"))
      (node (ref "U$1") (pin "39") (pinfunction "39_39") (pintype "passive"))
    )
    (net (code "107") (name "/VDD") (class "Default")
      (node (ref "U1") (pin "70") (pinfunction "P$70_70") (pintype "bidirectional"))
    )
    (net (code "108") (name "/VDD_B") (class "Default")
      (node (ref "C3") (pin "1") (pinfunction "1_1") (pintype "passive"))
      (node (ref "LVL_EN") (pin "2") (pinfunction "2_2") (pintype "passive"))
      (node (ref "R5") (pin "1") (pinfunction "1_1") (pintype "passive"))
      (node (ref "U2") (pin "19") (pinfunction "VDD_B_19") (pintype "bidirectional"))
      (node (ref "U2") (pin "20") (pinfunction "EN_20") (pintype "bidirectional"))
    )
    (net (code "109") (name "Net-(LED1-PadA)") (class "Default")
      (node (ref "LED1") (pin "A") (pinfunction "A_A") (pintype "passive"))
      (node (ref "R26") (pin "2") (pinfunction "2_2") (pintype "passive"))
    )
    (net (code "110") (name "Net-(LED1-PadC)") (class "Default")
      (node (ref "LED1") (pin "C") (pinfunction "C_C") (pintype "passive"))
      (node (ref "PB1") (pin "B2") (pinfunction "B2_B2") (pintype "bidirectional"))
    )
    (net (code "111") (name "Net-(LED2-PadA)") (class "Default")
      (node (ref "LED2") (pin "A") (pinfunction "A_A") (pintype "passive"))
      (node (ref "R27") (pin "2") (pinfunction "2_2") (pintype "passive"))
    )
    (net (code "112") (name "Net-(LED2-PadC)") (class "Default")
      (node (ref "LED2") (pin "C") (pinfunction "C_C") (pintype "passive"))
      (node (ref "PB2") (pin "B2") (pinfunction "B2_B2") (pintype "bidirectional"))
    )
    (net (code "113") (name "Net-(LED3-PadA)") (class "Default")
      (node (ref "LED3") (pin "A") (pinfunction "A_A") (pintype "passive"))
      (node (ref "R28") (pin "2") (pinfunction "2_2") (pintype "passive"))
    )
    (net (code "114") (name "Net-(LED3-PadC)") (class "Default")
      (node (ref "LED3") (pin "C") (pinfunction "C_C") (pintype "passive"))
      (node (ref "PB3") (pin "B2") (pinfunction "B2_B2") (pintype "bidirectional"))
    )
    (net (code "115") (name "Net-(LED4-PadA)") (class "Default")
      (node (ref "LED4") (pin "A") (pinfunction "A_A") (pintype "passive"))
      (node (ref "R29") (pin "2") (pinfunction "2_2") (pintype "passive"))
    )
    (net (code "116") (name "Net-(LED4-PadC)") (class "Default")
      (node (ref "LED4") (pin "C") (pinfunction "C_C") (pintype "passive"))
      (node (ref "PB4") (pin "B2") (pinfunction "B2_B2") (pintype "bidirectional"))
    )
    (net (code "117") (name "Net-(U3-RG+)") (class "Default")
      (node (ref "R1") (pin "2") (pinfunction "2_2") (pintype "passive"))
      (node (ref "U3") (pin "2") (pinfunction "RG+_2") (pintype "bidirectional"))
    )
    (net (code "118") (name "Net-(U3-RG-)") (class "Default")
      (node (ref "R1") (pin "1") (pinfunction "1_1") (pintype "passive"))
      (node (ref "U3") (pin "3") (pinfunction "RG-_3") (pintype "bidirectional"))
    )
    (net (code "119") (name "Net-(U3-VOUT)") (class "Default")
      (node (ref "R4") (pin "2") (pinfunction "2_2") (pintype "passive"))
      (node (ref "U3") (pin "7") (pinfunction "VOUT_7") (pintype "bidirectional"))
    )
    (net (code "120") (name "Net-(U4-RG+)") (class "Default")
      (node (ref "R2") (pin "2") (pinfunction "2_2") (pintype "passive"))
      (node (ref "U4") (pin "2") (pinfunction "RG+_2") (pintype "bidirectional"))
    )
    (net (code "121") (name "Net-(U4-RG-)") (class "Default")
      (node (ref "R2") (pin "1") (pinfunction "1_1") (pintype "passive"))
      (node (ref "U4") (pin "3") (pinfunction "RG-_3") (pintype "bidirectional"))
    )
    (net (code "122") (name "Net-(U4-VOUT)") (class "Default")
      (node (ref "R3") (pin "2") (pinfunction "2_2") (pintype "passive"))
      (node (ref "U4") (pin "7") (pinfunction "VOUT_7") (pintype "bidirectional"))
    )
    (net (code "123") (name "unconnected-(PB1-PadA1)") (class "Default")
      (node (ref "PB1") (pin "A1") (pinfunction "A1_A1") (pintype "bidirectional"))
    )
    (net (code "124") (name "unconnected-(PB1-PadA2)") (class "Default")
      (node (ref "PB1") (pin "A2") (pinfunction "A2_A2") (pintype "bidirectional"))
    )
    (net (code "125") (name "unconnected-(PB2-PadA1)") (class "Default")
      (node (ref "PB2") (pin "A1") (pinfunction "A1_A1") (pintype "bidirectional"))
    )
    (net (code "126") (name "unconnected-(PB2-PadA2)") (class "Default")
      (node (ref "PB2") (pin "A2") (pinfunction "A2_A2") (pintype "bidirectional"))
    )
    (net (code "127") (name "unconnected-(PB3-PadA1)") (class "Default")
      (node (ref "PB3") (pin "A1") (pinfunction "A1_A1") (pintype "bidirectional"))
    )
    (net (code "128") (name "unconnected-(PB3-PadA2)") (class "Default")
      (node (ref "PB3") (pin "A2") (pinfunction "A2_A2") (pintype "bidirectional"))
    )
    (net (code "129") (name "unconnected-(PB4-PadA1)") (class "Default")
      (node (ref "PB4") (pin "A1") (pinfunction "A1_A1") (pintype "bidirectional"))
    )
    (net (code "130") (name "unconnected-(PB4-PadA2)") (class "Default")
      (node (ref "PB4") (pin "A2") (pinfunction "A2_A2") (pintype "bidirectional"))
    )
    (net (code "131") (name "unconnected-(U1-P$98-Pad98)") (class "Default")
      (node (ref "U1") (pin "98") (pinfunction "P$98_98") (pintype "bidirectional"))
    )
  )
)
